# l293_board.net
KiCad netlist of a schematic drawn in EAGLE
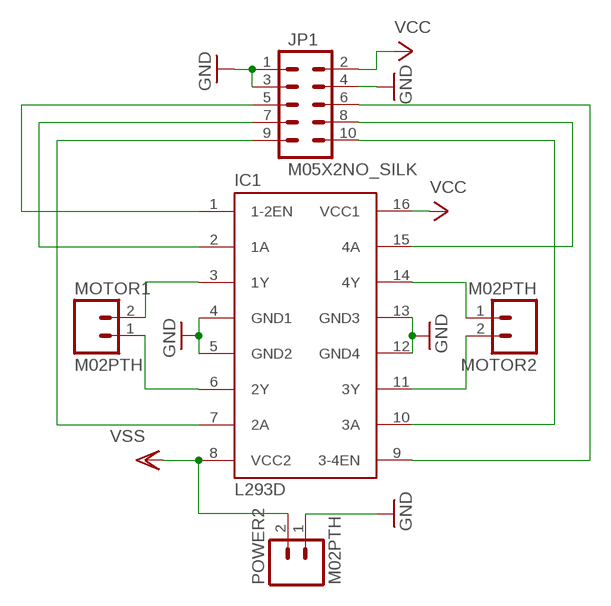
[diagram p0: schematic, sheet 1]

(export (version "E")
  (design (tool "Eeschema 10.0.6"))
  (components
    (comp (ref "IC1")
      (value "L293D")
      (footprint "eagle-import:DIL16")
      (libsource (lib "eagle-import") (part "L293D"))
    )
    (comp (ref "JP1")
      (value "M05X2NO_SILK")
      (footprint "eagle-import:2X5_NOSILK")
      (libsource (lib "eagle-import") (part "M05X2NO_SILK"))
    )
    (comp (ref "MOTOR1")
      (value "M02PTH")
      (footprint "eagle-import:1X02")
      (libsource (lib "eagle-import") (part "M02PTH"))
    )
    (comp (ref "MOTOR2")
      (value "M02PTH")
      (footprint "eagle-import:1X02")
      (libsource (lib "eagle-import") (part "M02PTH"))
    )
    (comp (ref "POWER2")
      (value "M02PTH")
      (footprint "eagle-import:1X02")
      (libsource (lib "eagle-import") (part "M02PTH"))
    )
  )
  (nets
    (net (code "1") (name "GND") (class "Default")
      (node (ref "IC1") (pin "12") (pinfunction "GND4_12") (pintype "power_in"))
      (node (ref "IC1") (pin "13") (pinfunction "GND3_13") (pintype "power_in"))
      (node (ref "IC1") (pin "4") (pinfunction "GND1_4") (pintype "power_in"))
      (node (ref "IC1") (pin "5") (pinfunction "GND2_5") (pintype "power_in"))
      (node (ref "JP1") (pin "1") (pinfunction "1_1") (pintype "passive"))
      (node (ref "JP1") (pin "3") (pinfunction "3_3") (pintype "passive"))
      (node (ref "JP1") (pin "4") (pinfunction "4_4") (pintype "passive"))
      (node (ref "POWER2") (pin "1") (pinfunction "1_1") (pintype "passive"))
    )
    (net (code "2") (name "Net-(IC1-1-2EN)") (class "Default")
      (node (ref "IC1") (pin "1") (pinfunction "1-2EN_1") (pintype "input"))
      (node (ref "JP1") (pin "5") (pinfunction "5_5") (pintype "passive"))
    )
    (net (code "3") (name "Net-(IC1-1A)") (class "Default")
      (node (ref "IC1") (pin "2") (pinfunction "1A_2") (pintype "input"))
      (node (ref "JP1") (pin "7") (pinfunction "7_7") (pintype "passive"))
    )
    (net (code "4") (name "Net-(IC1-1Y)") (class "Default")
      (node (ref "IC1") (pin "3") (pinfunction "1Y_3") (pintype "output"))
      (node (ref "MOTOR1") (pin "2") (pinfunction "2_2") (pintype "passive"))
    )
    (net (code "5") (name "Net-(IC1-2A)") (class "Default")
      (node (ref "IC1") (pin "7") (pinfunction "2A_7") (pintype "input"))
      (node (ref "JP1") (pin "9") (pinfunction "9_9") (pintype "passive"))
    )
    (net (code "6") (name "Net-(IC1-2Y)") (class "Default")
      (node (ref "IC1") (pin "6") (pinfunction "2Y_6") (pintype "output"))
      (node (ref "MOTOR1") (pin "1") (pinfunction "1_1") (pintype "passive"))
    )
    (net (code "7") (name "Net-(IC1-3-4EN)") (class "Default")
      (node (ref "IC1") (pin "9") (pinfunction "3-4EN_9") (pintype "input"))
      (node (ref "JP1") (pin "6") (pinfunction "6_6") (pintype "passive"))
    )
    (net (code "8") (name "Net-(IC1-3A)") (class "Default")
      (node (ref "IC1") (pin "10") (pinfunction "3A_10") (pintype "input"))
      (node (ref "JP1") (pin "10") (pinfunction "10_10") (pintype "passive"))
    )
    (net (code "9") (name "Net-(IC1-3Y)") (class "Default")
      (node (ref "IC1") (pin "11") (pinfunction "3Y_11") (pintype "output"))
      (node (ref "MOTOR2") (pin "2") (pinfunction "2_2") (pintype "passive"))
    )
    (net (code "10") (name "Net-(IC1-4A)") (class "Default")
      (node (ref "IC1") (pin "15") (pinfunction "4A_15") (pintype "input"))
      (node (ref "JP1") (pin "8") (pinfunction "8_8") (pintype "passive"))
    )
    (net (code "11") (name "Net-(IC1-4Y)") (class "Default")
      (node (ref "IC1") (pin "14") (pinfunction "4Y_14") (pintype "output"))
      (node (ref "MOTOR2") (pin "1") (pinfunction "1_1") (pintype "passive"))
    )
    (net (code "12") (name "VCC") (class "Default")
      (node (ref "IC1") (pin "16") (pinfunction "VCC1_16") (pintype "power_in"))
      (node (ref "JP1") (pin "2") (pinfunction "2_2") (pintype "passive"))
    )
    (net (code "13") (name "VSS") (class "Default")
      (node (ref "IC1") (pin "8") (pinfunction "VCC2_8") (pintype "power_in"))
      (node (ref "POWER2") (pin "2") (pinfunction "2_2") (pintype "passive"))
    )
  )
)
